# GeekTrack_SCH.net
KiCad netlist of a schematic drawn in Altium Designer
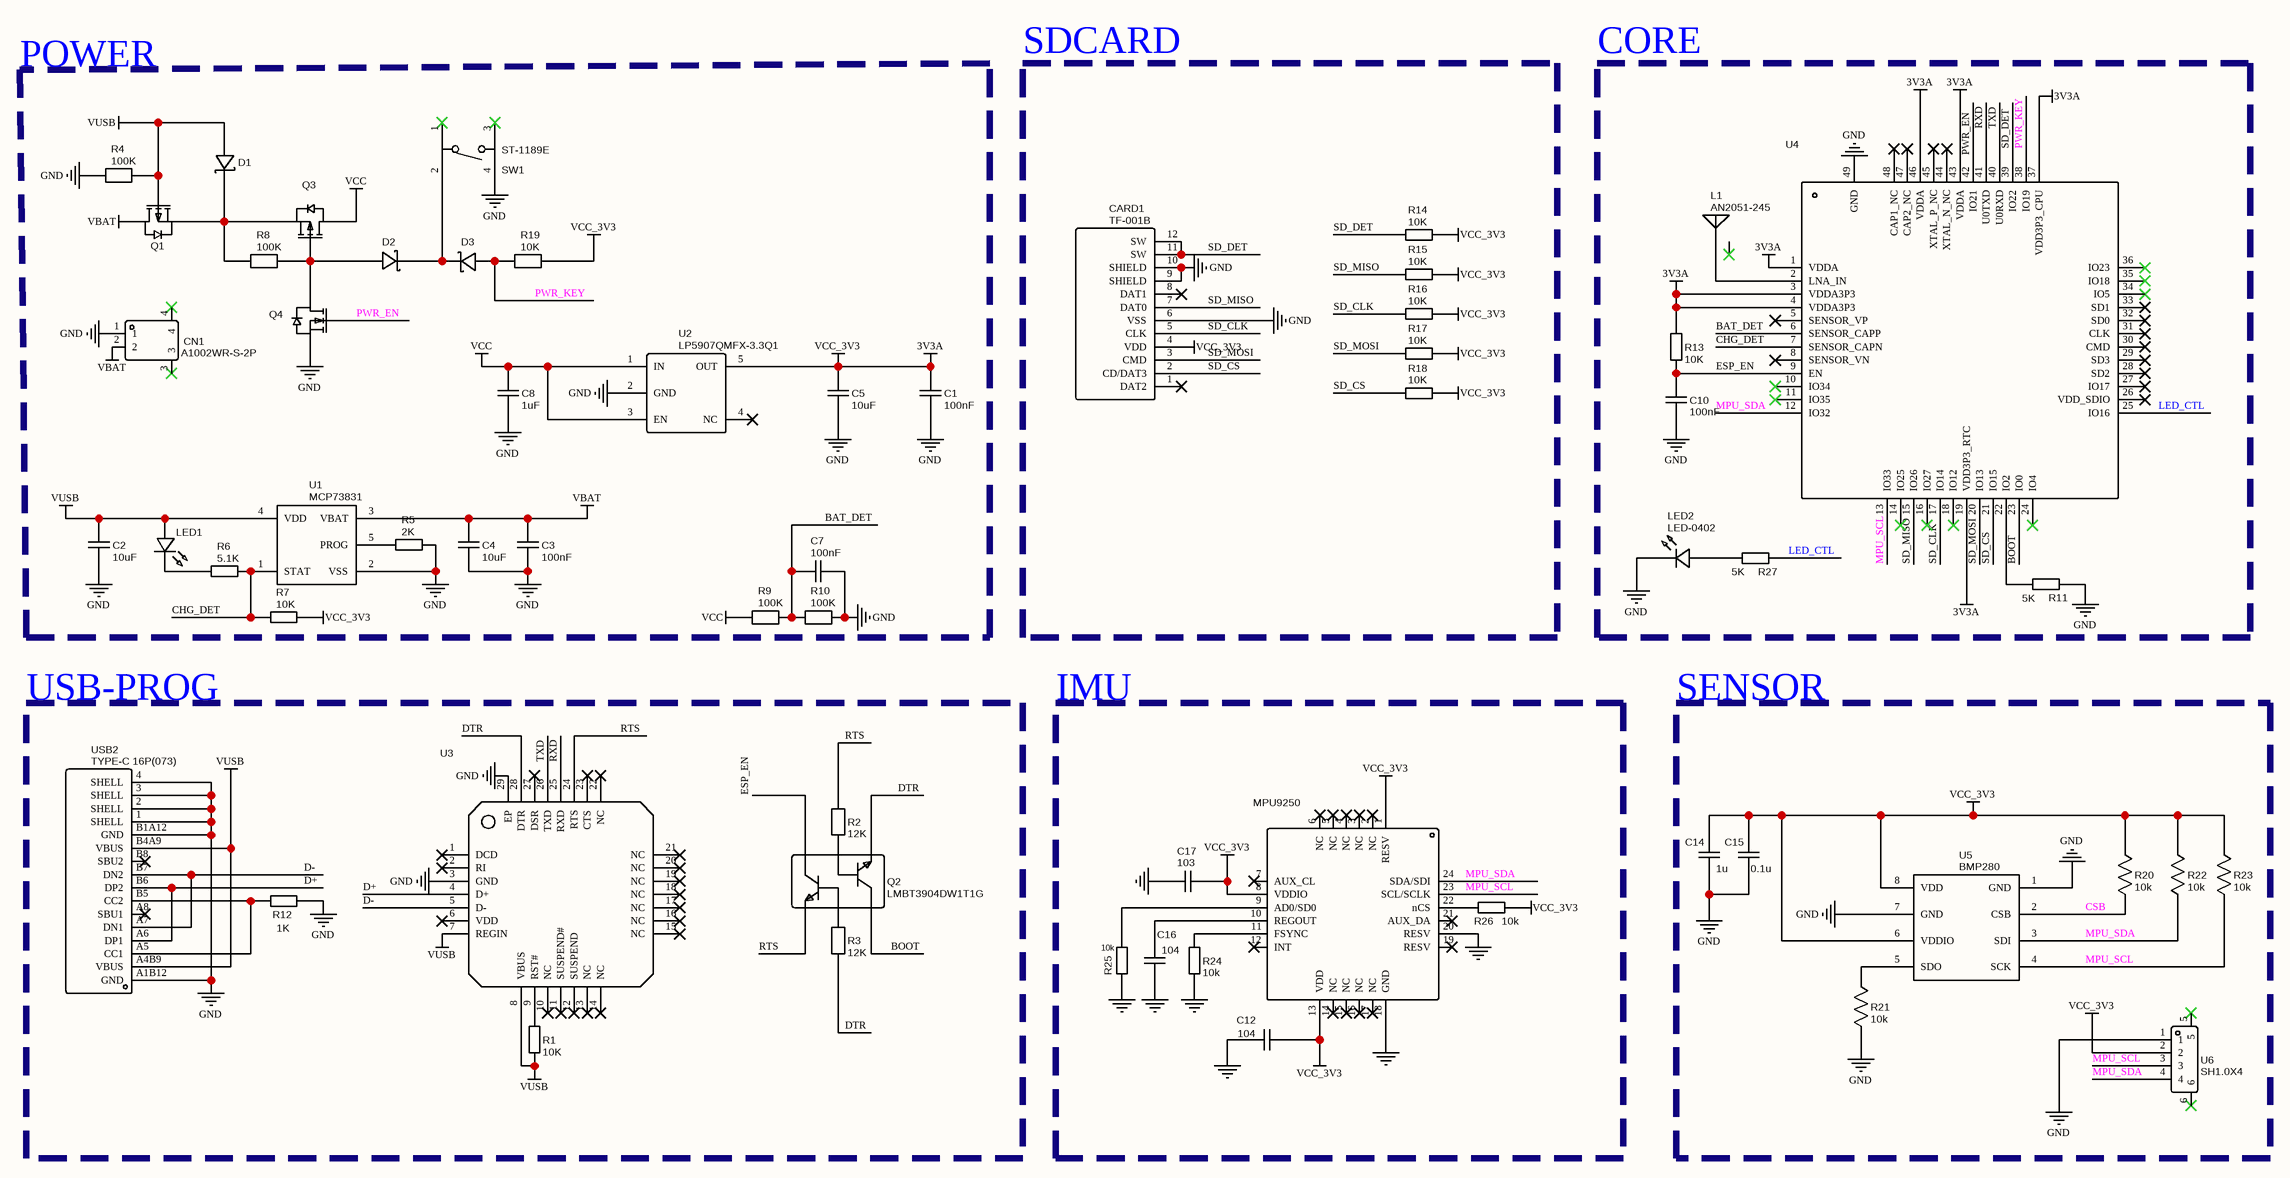
[diagram p0: GeekTrack_SCH.schdoc]

(export (version "E")
  (design (tool "Eeschema 10.0.6"))
  (components
    (comp (ref "C1")
      (value "100nF")
      (fields
        (field (name "BOM_SUPPLIER PART") "C541405")
        (field (name "BOM_MANUFACTURER PART") "CC0402KRX5R5BB104")
        (field (name "CONTRIBUTOR") "LCSC")
      )
      (libsource (lib "altium-import") (part "root_1_100nF_"))
    )
    (comp (ref "C2")
      (value "10uF")
      (fields
        (field (name "BOM_MANUFACTURER PART") "CL05A106MQ5NUNC")
        (field (name "BOM_SUPPLIER PART") "C15525")
      )
      (libsource (lib "altium-import") (part "root_1_10uF_"))
    )
    (comp (ref "C3")
      (value "100nF")
      (fields
        (field (name "BOM_SUPPLIER PART") "C541405")
        (field (name "BOM_MANUFACTURER PART") "CC0402KRX5R5BB104")
        (field (name "CONTRIBUTOR") "LCSC")
      )
      (libsource (lib "altium-import") (part "root_1_100nF_"))
    )
    (comp (ref "C4")
      (value "10uF")
      (fields
        (field (name "BOM_MANUFACTURER PART") "CL05A106MQ5NUNC")
        (field (name "BOM_SUPPLIER PART") "C15525")
      )
      (libsource (lib "altium-import") (part "root_1_10uF_"))
    )
    (comp (ref "C5")
      (value "10uF")
      (fields
        (field (name "BOM_SUPPLIER PART") "C141025")
        (field (name "BOM_MANUFACTURER PART") "C0402C105K9PAC7867")
        (field (name "CONTRIBUTOR") "LCSC")
      )
      (libsource (lib "altium-import") (part "root_0_10uF_"))
    )
    (comp (ref "C7")
      (value "100nF")
      (fields
        (field (name "BOM_SUPPLIER PART") "C541405")
        (field (name "BOM_MANUFACTURER PART") "CC0402KRX5R5BB104")
        (field (name "CONTRIBUTOR") "LCSC")
      )
      (libsource (lib "altium-import") (part "root_0_100nF_"))
    )
    (comp (ref "C8")
      (value "1uF")
      (fields
        (field (name "BOM_SUPPLIER PART") "C141025")
        (field (name "BOM_MANUFACTURER PART") "C0402C105K9PAC7867")
        (field (name "CONTRIBUTOR") "LCSC")
      )
      (libsource (lib "altium-import") (part "root_0_1uF_"))
    )
    (comp (ref "C10")
      (value "100nF")
      (fields
        (field (name "BOM_SUPPLIER PART") "C541405")
        (field (name "BOM_MANUFACTURER PART") "CC0402KRX5R5BB104")
        (field (name "CONTRIBUTOR") "LCSC")
      )
      (libsource (lib "altium-import") (part "root_1_100nF_"))
    )
    (comp (ref "C12")
      (value "104")
      (fields (field (name "BOM_MANUFACTURER PART") "?"))
      (libsource (lib "altium-import") (part "root_0_104_"))
    )
    (comp (ref "C14")
      (value "1u")
      (fields (field (name "CONTRIBUTOR") "LCEDA_Lib"))
      (libsource (lib "altium-import") (part "root_1_1u_"))
    )
    (comp (ref "C15")
      (value "0.1u")
      (fields (field (name "CONTRIBUTOR") "LCEDA_Lib"))
      (libsource (lib "altium-import") (part "root_1_0.1u_"))
    )
    (comp (ref "C16")
      (value "104")
      (fields (field (name "BOM_MANUFACTURER PART") "?"))
      (libsource (lib "altium-import") (part "root_1_104_"))
    )
    (comp (ref "C17")
      (value "103")
      (fields (field (name "BOM_MANUFACTURER PART") "?"))
      (libsource (lib "altium-import") (part "root_0_103_"))
    )
    (comp (ref "CARD1")
      (value "TF-001B")
      (fields (field (name "BOM_SUPPLIER PART") "C125617") (field (name "CONTRIBUTOR") "LCSC"))
      (libsource (lib "altium-import") (part "root_2_TF-001B_"))
    )
    (comp (ref "CN1")
      (value "A1002WR-S-2P")
      (fields (field (name "BOM_SUPPLIER PART") "C239520") (field (name "CONTRIBUTOR") "LCSC"))
      (libsource (lib "altium-import") (part "root_0_A1002WR-S-2P_"))
    )
    (comp (ref "D1")
      (value "B5819WS_C122855")
      (fields (field (name "BOM_MANUFACTURER PART") "B5819WS") (field (name "BOM_SUPPLIER PART") "C122855"))
      (libsource (lib "altium-import") (part "root_1_B5819WS_C122855_"))
    )
    (comp (ref "D2")
      (value "B5819WS_C122855")
      (fields (field (name "BOM_MANUFACTURER PART") "B5819WS") (field (name "BOM_SUPPLIER PART") "C122855"))
      (libsource (lib "altium-import") (part "root_2_B5819WS_C122855_"))
    )
    (comp (ref "D3")
      (value "B5819WS_C122855")
      (fields (field (name "BOM_MANUFACTURER PART") "B5819WS") (field (name "BOM_SUPPLIER PART") "C122855"))
      (libsource (lib "altium-import") (part "root_0_B5819WS_C122855_"))
    )
    (comp (ref "L1")
      (value "AN2051-245")
      (fields (field (name "BOM_SUPPLIER PART") "C99727"))
      (libsource (lib "altium-import") (part "root_0_AN2051-245_"))
    )
    (comp (ref "LED1")
      (value "LED-0603_R")
      (fields
        (field (name "BOM_MANUFACTURER PART") "19-217/R6C-AL1M2VY/3T")
        (field (name "BOM_SUPPLIER PART") "C72044")
        (field (name "CONTRIBUTOR") "LCEDA_01")
      )
      (libsource (lib "altium-import") (part "root_3_LED-0603_R_"))
    )
    (comp (ref "LED2")
      (value "LED-0402")
      (fields
        (field (name "BOM_SUPPLIER PART") "C917191")
        (field (name "BOM_MANUFACTURER PART") "TJ-S1005CL4T5ALC3DW-A5")
        (field (name "CONTRIBUTOR") "LCSC")
      )
      (libsource (lib "altium-import") (part "root_0_LED-0402_"))
    )
    (comp (ref "MPU9250")
      (value "MPU9250")
      (fields (field (name "BOM_MANUFACTURER PART") "?"))
      (libsource (lib "altium-import") (part "root_3_MPU9250_"))
    )
    (comp (ref "Q1")
      (value "AO3401A_C700954")
      (fields
        (field (name "BOM_SUPPLIER PART") "C700954")
        (field (name "BOM_MANUFACTURER PART") "AO3401A")
        (field (name "CONTRIBUTOR") "LCSC")
      )
      (libsource (lib "altium-import") (part "root_1_AO3401A_C700954_"))
    )
    (comp (ref "Q2")
      (value "LMBT3904DW1T1G")
      (fields (field (name "BOM_SUPPLIER PART") "C131781"))
      (libsource (lib "altium-import") (part "root_0_LMBT3904DW1T1G_"))
    )
    (comp (ref "Q3")
      (value "AO3401A_C700954")
      (fields
        (field (name "BOM_SUPPLIER PART") "C700954")
        (field (name "BOM_MANUFACTURER PART") "AO3401A")
        (field (name "CONTRIBUTOR") "LCSC")
      )
      (libsource (lib "altium-import") (part "root_3_AO3401A_C700954_"))
    )
    (comp (ref "Q4")
      (value "AO3400A_C700953")
      (fields
        (field (name "BOM_SUPPLIER PART") "C700953")
        (field (name "BOM_MANUFACTURER PART") "AO3400A")
        (field (name "CONTRIBUTOR") "LCSC")
      )
      (libsource (lib "altium-import") (part "root_2_AO3400A_C700953_"))
    )
    (comp (ref "R1")
      (value "10K")
      (fields
        (field (name "BOM_MANUFACTURER PART") "CR0402JF0103G")
        (field (name "BOM_SUPPLIER PART") "C100572")
      )
      (libsource (lib "altium-import") (part "root_1_10K_"))
    )
    (comp (ref "R2")
      (value "12K")
      (fields
        (field (name "BOM_SUPPLIER PART") "C881068")
        (field (name "BOM_MANUFACTURER PART") "CR0402F12K0Q10Z")
        (field (name "CONTRIBUTOR") "LCSC")
      )
      (libsource (lib "altium-import") (part "root_1_12K_"))
    )
    (comp (ref "R3")
      (value "12K")
      (fields
        (field (name "BOM_SUPPLIER PART") "C881068")
        (field (name "BOM_MANUFACTURER PART") "CR0402F12K0Q10Z")
        (field (name "CONTRIBUTOR") "LCSC")
      )
      (libsource (lib "altium-import") (part "root_1_12K_"))
    )
    (comp (ref "R4")
      (value "100K")
      (fields
        (field (name "BOM_SUPPLIER PART") "C881385")
        (field (name "BOM_MANUFACTURER PART") "CR0402F100KQ10Z")
        (field (name "CONTRIBUTOR") "LCSC")
      )
      (libsource (lib "altium-import") (part "root_0_100K_"))
    )
    (comp (ref "R5")
      (value "2K")
      (fields
        (field (name "BOM_MANUFACTURER PART") "CR0402FF2001G")
        (field (name "BOM_SUPPLIER PART") "C100291")
      )
      (libsource (lib "altium-import") (part "root_0_2K_"))
    )
    (comp (ref "R6")
      (value "5.1K")
      (fields
        (field (name "BOM_MANUFACTURER PART") "RC0402JR-071KL")
        (field (name "BOM_SUPPLIER PART") "C105637")
      )
      (libsource (lib "altium-import") (part "root_0_5.1K_"))
    )
    (comp (ref "R7")
      (value "10K")
      (fields
        (field (name "BOM_MANUFACTURER PART") "CR0402JF0103G")
        (field (name "BOM_SUPPLIER PART") "C100572")
      )
      (libsource (lib "") (part "root_0_10K__1"))
    )
    (comp (ref "R8")
      (value "100K")
      (fields
        (field (name "BOM_SUPPLIER PART") "C881385")
        (field (name "BOM_MANUFACTURER PART") "CR0402F100KQ10Z")
        (field (name "CONTRIBUTOR") "LCSC")
      )
      (libsource (lib "altium-import") (part "root_0_100K_"))
    )
    (comp (ref "R9")
      (value "100K")
      (fields
        (field (name "BOM_SUPPLIER PART") "C881385")
        (field (name "BOM_MANUFACTURER PART") "CR0402F100KQ10Z")
        (field (name "CONTRIBUTOR") "LCSC")
      )
      (libsource (lib "altium-import") (part "root_0_100K_"))
    )
    (comp (ref "R10")
      (value "100K")
      (fields
        (field (name "BOM_SUPPLIER PART") "C881385")
        (field (name "BOM_MANUFACTURER PART") "CR0402F100KQ10Z")
        (field (name "CONTRIBUTOR") "LCSC")
      )
      (libsource (lib "altium-import") (part "root_0_100K_"))
    )
    (comp (ref "R11")
      (value "5K")
      (fields
        (field (name "BOM_MANUFACTURER PART") "CR0402JF0103G")
        (field (name "BOM_SUPPLIER PART") "C100572")
      )
      (libsource (lib "altium-import") (part "root_2_5K_"))
    )
    (comp (ref "R12")
      (value "1K")
      (fields
        (field (name "BOM_MANUFACTURER PART") "RC0402JR-071KL")
        (field (name "BOM_SUPPLIER PART") "C105637")
      )
      (libsource (lib "altium-import") (part "root_0_1K_"))
    )
    (comp (ref "R13")
      (value "10K")
      (fields
        (field (name "BOM_MANUFACTURER PART") "CR0402JF0103G")
        (field (name "BOM_SUPPLIER PART") "C100572")
      )
      (libsource (lib "altium-import") (part "root_1_10K_"))
    )
    (comp (ref "R14")
      (value "10K")
      (fields
        (field (name "BOM_MANUFACTURER PART") "CR0402JF0103G")
        (field (name "BOM_SUPPLIER PART") "C100572")
      )
      (libsource (lib "altium-import") (part "root_2_10K_"))
    )
    (comp (ref "R15")
      (value "10K")
      (fields
        (field (name "BOM_MANUFACTURER PART") "CR0402JF0103G")
        (field (name "BOM_SUPPLIER PART") "C100572")
      )
      (libsource (lib "altium-import") (part "root_2_10K_"))
    )
    (comp (ref "R16")
      (value "10K")
      (fields
        (field (name "BOM_MANUFACTURER PART") "CR0402JF0103G")
        (field (name "BOM_SUPPLIER PART") "C100572")
      )
      (libsource (lib "altium-import") (part "root_2_10K_"))
    )
    (comp (ref "R17")
      (value "10K")
      (fields
        (field (name "BOM_MANUFACTURER PART") "CR0402JF0103G")
        (field (name "BOM_SUPPLIER PART") "C100572")
      )
      (libsource (lib "altium-import") (part "root_2_10K_"))
    )
    (comp (ref "R18")
      (value "10K")
      (fields
        (field (name "BOM_MANUFACTURER PART") "CR0402JF0103G")
        (field (name "BOM_SUPPLIER PART") "C100572")
      )
      (libsource (lib "altium-import") (part "root_2_10K_"))
    )
    (comp (ref "R19")
      (value "10K")
      (fields
        (field (name "BOM_SUPPLIER PART") "C881385")
        (field (name "BOM_MANUFACTURER PART") "CR0402F100KQ10Z")
        (field (name "CONTRIBUTOR") "LCSC")
      )
      (libsource (lib "altium-import") (part "root_0_10K_"))
    )
    (comp (ref "R20")
      (value "10k")
      (fields (field (name "CONTRIBUTOR") "LCEDA_Lib"))
      (libsource (lib "altium-import") (part "root_1_10k_"))
    )
    (comp (ref "R21")
      (value "10k")
      (fields (field (name "CONTRIBUTOR") "LCEDA_Lib"))
      (libsource (lib "altium-import") (part "root_1_10k_"))
    )
    (comp (ref "R22")
      (value "10k")
      (fields (field (name "CONTRIBUTOR") "LCEDA_Lib"))
      (libsource (lib "altium-import") (part "root_1_10k_"))
    )
    (comp (ref "R23")
      (value "10k")
      (fields (field (name "CONTRIBUTOR") "LCEDA_Lib"))
      (libsource (lib "altium-import") (part "root_1_10k_"))
    )
    (comp (ref "R24")
      (value "10k")
      (fields (field (name "BOM_MANUFACTURER PART") "?"))
      (libsource (lib "altium-import") (part "root_3_10k_"))
    )
    (comp (ref "R25")
      (value "10k")
      (fields (field (name "BOM_MANUFACTURER PART") "?"))
      (libsource (lib "") (part "root_1_10k__1"))
    )
    (comp (ref "R26")
      (value "10k")
      (fields (field (name "BOM_MANUFACTURER PART") "?"))
      (libsource (lib "altium-import") (part "root_0_10k_"))
    )
    (comp (ref "R27")
      (value "5K")
      (fields
        (field (name "BOM_MANUFACTURER PART") "CR0402JF0103G")
        (field (name "BOM_SUPPLIER PART") "C100572")
      )
      (libsource (lib "altium-import") (part "root_2_5K_"))
    )
    (comp (ref "SW1")
      (value "ST-1189E")
      (fields (field (name "BOM_SUPPLIER PART") "C589215") (field (name "CONTRIBUTOR") "LCSC"))
      (libsource (lib "altium-import") (part "root_1_ST-1189E_"))
    )
    (comp (ref "U1")
      (value "MCP73831")
      (fields
        (field (name "BOM_MANUFACTURER PART") "MCP73831T-2ATI/OT")
        (field (name "BOM_SUPPLIER PART") "C14879")
      )
      (libsource (lib "altium-import") (part "root_0_MCP73831_"))
    )
    (comp (ref "U2")
      (value "LP5907QMFX-3.3Q1")
      (fields (field (name "BOM_SUPPLIER PART") "C130005") (field (name "CONTRIBUTOR") "LCSC"))
      (libsource (lib "altium-import") (part "root_0_LP5907QMFX-3.3Q1_"))
    )
    (comp (ref "U3")
      (value "CP2102-GMR")
      (fields (field (name "BOM_SUPPLIER PART") "C6568"))
      (libsource (lib "altium-import") (part "root_0_CP2102-GMR_"))
    )
    (comp (ref "U4")
      (value "ESP32-PICO-D4")
      (fields (field (name "BOM_SUPPLIER PART") "C193707") (field (name "CONTRIBUTOR") "DGrain"))
      (libsource (lib "altium-import") (part "root_0_ESP32-PICO-D4_"))
    )
    (comp (ref "U5")
      (value "BMP280")
      (fields (field (name "BOM_SUPPLIER PART") "C83291"))
      (libsource (lib "altium-import") (part "root_0_BMP280_"))
    )
    (comp (ref "U6")
      (value "SH1.0X4")
      (fields
        (field (name "BOM_SUPPLIER PART") "C9900002342")
        (field (name "BOM_MANUFACTURER PART") "SH1.0X4卧贴")
        (field (name "CONTRIBUTOR") "LCSC")
      )
      (libsource (lib "altium-import") (part "root_0_SH1.0X4_"))
    )
    (comp (ref "USB2")
      (value "TYPE-C 16P(073)")
      (fields (field (name "BOM_SUPPLIER PART") "C668624") (field (name "CONTRIBUTOR") "LCSC"))
      (libsource (lib "altium-import") (part "root_2_TYPE-C 16P(073)_"))
    )
  )
  (nets
    (net (code "1") (name "/BAT_DET") (class "Default")
      (node (ref "C7") (pin "1") (pinfunction "1_1") (pintype "passive"))
      (node (ref "R10") (pin "1") (pinfunction "1_1") (pintype "passive"))
      (node (ref "R9") (pin "2") (pinfunction "2_2") (pintype "passive"))
      (node (ref "U4") (pin "6") (pinfunction "SENSOR_CAPP_6") (pintype "passive"))
    )
    (net (code "2") (name "/BOOT") (class "Default")
      (node (ref "Q2") (pin "3") (pinfunction "C_3") (pintype "passive"))
      (node (ref "U4") (pin "23") (pinfunction "IO0_23") (pintype "passive"))
    )
    (net (code "3") (name "/CHG_DET") (class "Default")
      (node (ref "R6") (pin "2") (pinfunction "2_2") (pintype "passive"))
      (node (ref "R7") (pin "1") (pinfunction "1_1") (pintype "passive"))
      (node (ref "U1") (pin "1") (pinfunction "STAT_1") (pintype "passive"))
      (node (ref "U4") (pin "7") (pinfunction "SENSOR_CAPN_7") (pintype "passive"))
    )
    (net (code "4") (name "/CSB") (class "Default")
      (node (ref "R20") (pin "1") (pinfunction "1_1") (pintype "passive"))
      (node (ref "U5") (pin "2") (pinfunction "CSB_2") (pintype "passive"))
    )
    (net (code "5") (name "/D+") (class "Default")
      (node (ref "U3") (pin "4") (pinfunction "D+_4") (pintype "passive"))
      (node (ref "USB2") (pin "A6") (pinfunction "DP1_A6") (pintype "passive"))
      (node (ref "USB2") (pin "B6") (pinfunction "DP2_B6") (pintype "passive"))
    )
    (net (code "6") (name "/D-") (class "Default")
      (node (ref "U3") (pin "5") (pinfunction "D-_5") (pintype "passive"))
      (node (ref "USB2") (pin "A7") (pinfunction "DN1_A7") (pintype "passive"))
      (node (ref "USB2") (pin "B7") (pinfunction "DN2_B7") (pintype "passive"))
    )
    (net (code "7") (name "/DTR") (class "Default")
      (node (ref "Q2") (pin "4") (pinfunction "E_4") (pintype "passive"))
      (node (ref "R3") (pin "1") (pinfunction "1_1") (pintype "passive"))
      (node (ref "U3") (pin "28") (pinfunction "DTR_28") (pintype "passive"))
    )
    (net (code "8") (name "/ESP_EN") (class "Default")
      (node (ref "C10") (pin "2") (pinfunction "2_2") (pintype "passive"))
      (node (ref "Q2") (pin "6") (pinfunction "C_6") (pintype "passive"))
      (node (ref "R13") (pin "1") (pinfunction "1_1") (pintype "passive"))
      (node (ref "U4") (pin "9") (pinfunction "EN_9") (pintype "passive"))
    )
    (net (code "9") (name "/LED_CTL") (class "Default")
      (node (ref "R27") (pin "1") (pinfunction "1_1") (pintype "passive"))
      (node (ref "U4") (pin "25") (pinfunction "IO16_25") (pintype "passive"))
    )
    (net (code "10") (name "/MPU_SCL") (class "Default")
      (node (ref "MPU9250") (pin "23") (pinfunction "SCL/SCLK_23") (pintype "passive"))
      (node (ref "R23") (pin "1") (pinfunction "1_1") (pintype "passive"))
      (node (ref "U4") (pin "13") (pinfunction "IO33_13") (pintype "passive"))
      (node (ref "U5") (pin "4") (pinfunction "SCK_4") (pintype "passive"))
      (node (ref "U6") (pin "3") (pinfunction "3_3") (pintype "passive"))
    )
    (net (code "11") (name "/MPU_SDA") (class "Default")
      (node (ref "MPU9250") (pin "24") (pinfunction "SDA/SDI_24") (pintype "passive"))
      (node (ref "R22") (pin "1") (pinfunction "1_1") (pintype "passive"))
      (node (ref "U4") (pin "12") (pinfunction "IO32_12") (pintype "passive"))
      (node (ref "U5") (pin "3") (pinfunction "SDI_3") (pintype "passive"))
      (node (ref "U6") (pin "4") (pinfunction "4_4") (pintype "passive"))
    )
    (net (code "12") (name "/PWR_EN") (class "Default")
      (node (ref "Q4") (pin "1") (pinfunction "G_1") (pintype "passive"))
      (node (ref "U4") (pin "42") (pinfunction "IO21_42") (pintype "passive"))
    )
    (net (code "13") (name "/PWR_KEY") (class "Default")
      (node (ref "D3") (pin "2") (pinfunction "A_2") (pintype "passive"))
      (node (ref "R19") (pin "1") (pinfunction "1_1") (pintype "passive"))
      (node (ref "U4") (pin "38") (pinfunction "IO19_38") (pintype "passive"))
    )
    (net (code "14") (name "/RTS") (class "Default")
      (node (ref "Q2") (pin "1") (pinfunction "E_1") (pintype "passive"))
      (node (ref "R2") (pin "2") (pinfunction "2_2") (pintype "passive"))
      (node (ref "U3") (pin "24") (pinfunction "RTS_24") (pintype "passive"))
    )
    (net (code "15") (name "/RXD") (class "Default")
      (node (ref "U3") (pin "25") (pinfunction "RXD_25") (pintype "passive"))
      (node (ref "U4") (pin "41") (pinfunction "U0TXD_41") (pintype "passive"))
    )
    (net (code "16") (name "/SD_CLK") (class "Default")
      (node (ref "CARD1") (pin "5") (pinfunction "CLK_5") (pintype "passive"))
      (node (ref "R16") (pin "2") (pinfunction "2_2") (pintype "passive"))
      (node (ref "U4") (pin "17") (pinfunction "IO14_17") (pintype "passive"))
    )
    (net (code "17") (name "/SD_CS") (class "Default")
      (node (ref "CARD1") (pin "2") (pinfunction "CD/DAT3_2") (pintype "passive"))
      (node (ref "R18") (pin "2") (pinfunction "2_2") (pintype "passive"))
      (node (ref "U4") (pin "21") (pinfunction "IO15_21") (pintype "passive"))
    )
    (net (code "18") (name "/SD_DET") (class "Default")
      (node (ref "CARD1") (pin "11") (pinfunction "SW_11") (pintype "passive"))
      (node (ref "CARD1") (pin "12") (pinfunction "SW_12") (pintype "passive"))
      (node (ref "R14") (pin "2") (pinfunction "2_2") (pintype "passive"))
      (node (ref "U4") (pin "39") (pinfunction "IO22_39") (pintype "passive"))
    )
    (net (code "19") (name "/SD_MISO") (class "Default")
      (node (ref "CARD1") (pin "7") (pinfunction "DAT0_7") (pintype "passive"))
      (node (ref "R15") (pin "2") (pinfunction "2_2") (pintype "passive"))
      (node (ref "U4") (pin "15") (pinfunction "IO26_15") (pintype "passive"))
    )
    (net (code "20") (name "/SD_MOSI") (class "Default")
      (node (ref "CARD1") (pin "3") (pinfunction "CMD_3") (pintype "passive"))
      (node (ref "R17") (pin "2") (pinfunction "2_2") (pintype "passive"))
      (node (ref "U4") (pin "20") (pinfunction "IO13_20") (pintype "passive"))
    )
    (net (code "21") (name "/TXD") (class "Default")
      (node (ref "U3") (pin "26") (pinfunction "TXD_26") (pintype "passive"))
      (node (ref "U4") (pin "40") (pinfunction "U0RXD_40") (pintype "passive"))
    )
    (net (code "22") (name "3V3A") (class "Default")
      (node (ref "C1") (pin "2") (pinfunction "2_2") (pintype "passive"))
      (node (ref "C12") (pin "2") (pinfunction "2_2") (pintype "passive"))
      (node (ref "C14") (pin "2") (pinfunction "2_2") (pintype "passive"))
      (node (ref "C15") (pin "2") (pinfunction "2_2") (pintype "passive"))
      (node (ref "C17") (pin "2") (pinfunction "2_2") (pintype "passive"))
      (node (ref "C5") (pin "2") (pinfunction "2_2") (pintype "passive"))
      (node (ref "CARD1") (pin "4") (pinfunction "VDD_4") (pintype "passive"))
      (node (ref "MPU9250") (pin "1") (pinfunction "RESV_1") (pintype "passive"))
      (node (ref "MPU9250") (pin "13") (pinfunction "VDD_13") (pintype "passive"))
      (node (ref "MPU9250") (pin "8") (pinfunction "VDDIO_8") (pintype "passive"))
      (node (ref "R13") (pin "2") (pinfunction "2_2") (pintype "passive"))
      (node (ref "R14") (pin "1") (pinfunction "1_1") (pintype "passive"))
      (node (ref "R15") (pin "1") (pinfunction "1_1") (pintype "passive"))
      (node (ref "R16") (pin "1") (pinfunction "1_1") (pintype "passive"))
      (node (ref "R17") (pin "1") (pinfunction "1_1") (pintype "passive"))
      (node (ref "R18") (pin "1") (pinfunction "1_1") (pintype "passive"))
      (node (ref "R19") (pin "2") (pinfunction "2_2") (pintype "passive"))
      (node (ref "R20") (pin "2") (pinfunction "2_2") (pintype "passive"))
      (node (ref "R22") (pin "2") (pinfunction "2_2") (pintype "passive"))
      (node (ref "R23") (pin "2") (pinfunction "2_2") (pintype "passive"))
      (node (ref "R26") (pin "2") (pinfunction "2_2") (pintype "passive"))
      (node (ref "R7") (pin "2") (pinfunction "2_2") (pintype "passive"))
      (node (ref "U2") (pin "5") (pinfunction "OUT_5") (pintype "passive"))
      (node (ref "U4") (pin "1") (pinfunction "VDDA_1") (pintype "passive"))
      (node (ref "U4") (pin "19") (pinfunction "VDD3P3_RTC_19") (pintype "passive"))
      (node (ref "U4") (pin "3") (pinfunction "VDDA3P3_3") (pintype "passive"))
      (node (ref "U4") (pin "37") (pinfunction "VDD3P3_CPU_37") (pintype "passive"))
      (node (ref "U4") (pin "4") (pinfunction "VDDA3P3_4") (pintype "passive"))
      (node (ref "U4") (pin "43") (pinfunction "VDDA_43") (pintype "passive"))
      (node (ref "U4") (pin "46") (pinfunction "VDDA_46") (pintype "passive"))
      (node (ref "U5") (pin "6") (pinfunction "VDDIO_6") (pintype "passive"))
      (node (ref "U5") (pin "8") (pinfunction "VDD_8") (pintype "passive"))
      (node (ref "U6") (pin "2") (pinfunction "2_2") (pintype "passive"))
    )
    (net (code "23") (name "GND") (class "Default")
      (node (ref "C1") (pin "1") (pinfunction "1_1") (pintype "passive"))
      (node (ref "C10") (pin "1") (pinfunction "1_1") (pintype "passive"))
      (node (ref "C12") (pin "1") (pinfunction "1_1") (pintype "passive"))
      (node (ref "C14") (pin "1") (pinfunction "1_1") (pintype "passive"))
      (node (ref "C15") (pin "1") (pinfunction "1_1") (pintype "passive"))
      (node (ref "C16") (pin "1") (pinfunction "1_1") (pintype "passive"))
      (node (ref "C17") (pin "1") (pinfunction "1_1") (pintype "passive"))
      (node (ref "C2") (pin "1") (pinfunction "1_1") (pintype "passive"))
      (node (ref "C3") (pin "1") (pinfunction "1_1") (pintype "passive"))
      (node (ref "C4") (pin "1") (pinfunction "1_1") (pintype "passive"))
      (node (ref "C5") (pin "1") (pinfunction "1_1") (pintype "passive"))
      (node (ref "C7") (pin "2") (pinfunction "2_2") (pintype "passive"))
      (node (ref "C8") (pin "1") (pinfunction "1_1") (pintype "passive"))
      (node (ref "CARD1") (pin "10") (pinfunction "SHIELD_10") (pintype "passive"))
      (node (ref "CARD1") (pin "6") (pinfunction "VSS_6") (pintype "passive"))
      (node (ref "CARD1") (pin "9") (pinfunction "SHIELD_9") (pintype "passive"))
      (node (ref "CN1") (pin "1") (pinfunction "1_1") (pintype "passive"))
      (node (ref "LED2") (pin "1") (pinfunction "K_1") (pintype "passive"))
      (node (ref "MPU9250") (pin "18") (pinfunction "GND_18") (pintype "passive"))
      (node (ref "MPU9250") (pin "20") (pinfunction "RESV_20") (pintype "passive"))
      (node (ref "Q4") (pin "2") (pinfunction "S_2") (pintype "passive"))
      (node (ref "R10") (pin "2") (pinfunction "2_2") (pintype "passive"))
      (node (ref "R11") (pin "1") (pinfunction "1_1") (pintype "passive"))
      (node (ref "R12") (pin "2") (pinfunction "2_2") (pintype "passive"))
      (node (ref "R21") (pin "1") (pinfunction "1_1") (pintype "passive"))
      (node (ref "R24") (pin "2") (pinfunction "2_2") (pintype "passive"))
      (node (ref "R25") (pin "1") (pinfunction "1_1") (pintype "passive"))
      (node (ref "R4") (pin "1") (pinfunction "1_1") (pintype "passive"))
      (node (ref "R5") (pin "2") (pinfunction "2_2") (pintype "passive"))
      (node (ref "SW1") (pin "4") (pinfunction "4_4") (pintype "passive"))
      (node (ref "U1") (pin "2") (pinfunction "VSS_2") (pintype "passive"))
      (node (ref "U2") (pin "2") (pinfunction "GND_2") (pintype "passive"))
      (node (ref "U3") (pin "29") (pinfunction "EP_29") (pintype "passive"))
      (node (ref "U3") (pin "3") (pinfunction "GND_3") (pintype "passive"))
      (node (ref "U4") (pin "49") (pinfunction "GND_49") (pintype "passive"))
      (node (ref "U5") (pin "1") (pinfunction "GND_1") (pintype "passive"))
      (node (ref "U5") (pin "7") (pinfunction "GND_7") (pintype "passive"))
      (node (ref "U6") (pin "1") (pinfunction "1_1") (pintype "passive"))
      (node (ref "USB2") (pin "1") (pinfunction "SHELL_1") (pintype "passive"))
      (node (ref "USB2") (pin "2") (pinfunction "SHELL_2") (pintype "passive"))
      (node (ref "USB2") (pin "3") (pinfunction "SHELL_3") (pintype "passive"))
      (node (ref "USB2") (pin "4") (pinfunction "SHELL_4") (pintype "passive"))
      (node (ref "USB2") (pin "A1B12") (pinfunction "GND_A1B12") (pintype "passive"))
      (node (ref "USB2") (pin "B1A12") (pinfunction "GND_B1A12") (pintype "passive"))
    )
    (net (code "24") (name "Net-(D1-K)") (class "Default")
      (node (ref "D1") (pin "1") (pinfunction "K_1") (pintype "passive"))
      (node (ref "Q1") (pin "2") (pinfunction "S_2") (pintype "passive"))
      (node (ref "Q3") (pin "2") (pinfunction "S_2") (pintype "passive"))
      (node (ref "R8") (pin "1") (pinfunction "1_1") (pintype "passive"))
    )
    (net (code "25") (name "Net-(D2-A)") (class "Default")
      (node (ref "D2") (pin "2") (pinfunction "A_2") (pintype "passive"))
      (node (ref "Q3") (pin "1") (pinfunction "G_1") (pintype "passive"))
      (node (ref "Q4") (pin "3") (pinfunction "D_3") (pintype "passive"))
      (node (ref "R8") (pin "2") (pinfunction "2_2") (pintype "passive"))
    )
    (net (code "26") (name "Net-(D2-K)") (class "Default")
      (node (ref "D2") (pin "1") (pinfunction "K_1") (pintype "passive"))
      (node (ref "D3") (pin "1") (pinfunction "K_1") (pintype "passive"))
      (node (ref "SW1") (pin "2") (pinfunction "2_2") (pintype "passive"))
    )
    (net (code "27") (name "Net-(L1-ANT)") (class "Default")
      (node (ref "L1") (pin "1") (pinfunction "ANT_1") (pintype "passive"))
      (node (ref "U4") (pin "2") (pinfunction "LNA_IN_2") (pintype "passive"))
    )
    (net (code "28") (name "Net-(LED1-Pad2)") (class "Default")
      (node (ref "LED1") (pin "2") (pinfunction "2_2") (pintype "passive"))
      (node (ref "R6") (pin "1") (pinfunction "1_1") (pintype "passive"))
    )
    (net (code "29") (name "Net-(LED2-A)") (class "Default")
      (node (ref "LED2") (pin "2") (pinfunction "A_2") (pintype "passive"))
      (node (ref "R27") (pin "2") (pinfunction "2_2") (pintype "passive"))
    )
    (net (code "30") (name "Net-(MPU9250-AD0{slash}SD0)") (class "Default")
      (node (ref "MPU9250") (pin "9") (pinfunction "AD0/SD0_9") (pintype "passive"))
      (node (ref "R25") (pin "2") (pinfunction "2_2") (pintype "passive"))
    )
    (net (code "31") (name "Net-(MPU9250-FSYNC)") (class "Default")
      (node (ref "MPU9250") (pin "11") (pinfunction "FSYNC_11") (pintype "passive"))
      (node (ref "R24") (pin "1") (pinfunction "1_1") (pintype "passive"))
    )
    (net (code "32") (name "Net-(MPU9250-REGOUT)") (class "Default")
      (node (ref "C16") (pin "2") (pinfunction "2_2") (pintype "passive"))
      (node (ref "MPU9250") (pin "10") (pinfunction "REGOUT_10") (pintype "passive"))
    )
    (net (code "33") (name "Net-(MPU9250-nCS)") (class "Default")
      (node (ref "MPU9250") (pin "22") (pinfunction "nCS_22") (pintype "passive"))
      (node (ref "R26") (pin "1") (pinfunction "1_1") (pintype "passive"))
    )
    (net (code "34") (name "Net-(Q2-B-Pad2)") (class "Default")
      (node (ref "Q2") (pin "2") (pinfunction "B_2") (pintype "passive"))
      (node (ref "R3") (pin "2") (pinfunction "2_2") (pintype "passive"))
    )
    (net (code "35") (name "Net-(Q2-B-Pad5)") (class "Default")
      (node (ref "Q2") (pin "5") (pinfunction "B_5") (pintype "passive"))
      (node (ref "R2") (pin "1") (pinfunction "1_1") (pintype "passive"))
    )
    (net (code "36") (name "Net-(U1-PROG)") (class "Default")
      (node (ref "R5") (pin "1") (pinfunction "1_1") (pintype "passive"))
      (node (ref "U1") (pin "5") (pinfunction "PROG_5") (pintype "passive"))
    )
    (net (code "37") (name "Net-(U3-RST#)") (class "Default")
      (node (ref "R1") (pin "2") (pinfunction "2_2") (pintype "passive"))
      (node (ref "U3") (pin "9") (pinfunction "RST#_9") (pintype "passive"))
    )
    (net (code "38") (name "Net-(U4-IO2)") (class "Default")
      (node (ref "R11") (pin "2") (pinfunction "2_2") (pintype "passive"))
      (node (ref "U4") (pin "22") (pinfunction "IO2_22") (pintype "passive"))
    )
    (net (code "39") (name "Net-(U5-SDO)") (class "Default")
      (node (ref "R21") (pin "2") (pinfunction "2_2") (pintype "passive"))
      (node (ref "U5") (pin "5") (pinfunction "SDO_5") (pintype "passive"))
    )
    (net (code "40") (name "Net-(USB2-CC1)") (class "Default")
      (node (ref "R12") (pin "1") (pinfunction "1_1") (pintype "passive"))
      (node (ref "USB2") (pin "A5") (pinfunction "CC1_A5") (pintype "passive"))
      (node (ref "USB2") (pin "B5") (pinfunction "CC2_B5") (pintype "passive"))
    )
    (net (code "41") (name "VBAT") (class "Default")
      (node (ref "C3") (pin "2") (pinfunction "2_2") (pintype "passive"))
      (node (ref "C4") (pin "2") (pinfunction "2_2") (pintype "passive"))
      (node (ref "CN1") (pin "2") (pinfunction "2_2") (pintype "passive"))
      (node (ref "Q1") (pin "3") (pinfunction "D_3") (pintype "passive"))
      (node (ref "U1") (pin "3") (pinfunction "VBAT_3") (pintype "passive"))
    )
    (net (code "42") (name "VCC") (class "Default")
      (node (ref "C8") (pin "2") (pinfunction "2_2") (pintype "passive"))
      (node (ref "Q3") (pin "3") (pinfunction "D_3") (pintype "passive"))
      (node (ref "R9") (pin "1") (pinfunction "1_1") (pintype "passive"))
      (node (ref "U2") (pin "1") (pinfunction "IN_1") (pintype "passive"))
      (node (ref "U2") (pin "3") (pinfunction "EN_3") (pintype "passive"))
    )
    (net (code "43") (name "VUSB") (class "Default")
      (node (ref "C2") (pin "2") (pinfunction "2_2") (pintype "passive"))
      (node (ref "D1") (pin "2") (pinfunction "A_2") (pintype "passive"))
      (node (ref "LED1") (pin "1") (pinfunction "1_1") (pintype "passive"))
      (node (ref "Q1") (pin "1") (pinfunction "G_1") (pintype "passive"))
      (node (ref "R1") (pin "1") (pinfunction "1_1") (pintype "passive"))
      (node (ref "R4") (pin "2") (pinfunction "2_2") (pintype "passive"))
      (node (ref "U1") (pin "4") (pinfunction "VDD_4") (pintype "passive"))
      (node (ref "U3") (pin "7") (pinfunction "REGIN_7") (pintype "passive"))
      (node (ref "U3") (pin "8") (pinfunction "VBUS_8") (pintype "passive"))
      (node (ref "USB2") (pin "A4B9") (pinfunction "VBUS_A4B9") (pintype "passive"))
      (node (ref "USB2") (pin "B4A9") (pinfunction "VBUS_B4A9") (pintype "passive"))
    )
    (net (code "44") (name "unconnected-(CARD1-DAT1-Pad8)") (class "Default")
      (node (ref "CARD1") (pin "8") (pinfunction "DAT1_8") (pintype "passive+no_connect"))
    )
    (net (code "45") (name "unconnected-(CARD1-DAT2-Pad1)") (class "Default")
      (node (ref "CARD1") (pin "1") (pinfunction "DAT2_1") (pintype "passive+no_connect"))
    )
    (net (code "46") (name "unconnected-(CN1-Pad3)") (class "Default")
      (node (ref "CN1") (pin "3") (pinfunction "3_3") (pintype "passive+no_connect"))
    )
    (net (code "47") (name "unconnected-(CN1-Pad4)") (class "Default")
      (node (ref "CN1") (pin "4") (pinfunction "4_4") (pintype "passive+no_connect"))
    )
    (net (code "48") (name "unconnected-(L1-Pad2)") (class "Default")
      (node (ref "L1") (pin "2") (pinfunction "2_2") (pintype "passive+no_connect"))
    )
    (net (code "49") (name "unconnected-(MPU9250-AUX_CL-Pad7)") (class "Default")
      (node (ref "MPU9250") (pin "7") (pinfunction "AUX_CL_7") (pintype "passive+no_connect"))
    )
    (net (code "50") (name "unconnected-(MPU9250-AUX_DA-Pad21)") (class "Default")
      (node (ref "MPU9250") (pin "21") (pinfunction "AUX_DA_21") (pintype "passive+no_connect"))
    )
    (net (code "51") (name "unconnected-(MPU9250-INT-Pad12)") (class "Default")
      (node (ref "MPU9250") (pin "12") (pinfunction "INT_12") (pintype "passive+no_connect"))
    )
    (net (code "52") (name "unconnected-(MPU9250-NC-Pad2)") (class "Default")
      (node (ref "MPU9250") (pin "2") (pinfunction "NC_2") (pintype "passive+no_connect"))
    )
    (net (code "53") (name "unconnected-(MPU9250-NC-Pad3)") (class "Default")
      (node (ref "MPU9250") (pin "3") (pinfunction "NC_3") (pintype "passive+no_connect"))
    )
    (net (code "54") (name "unconnected-(MPU9250-NC-Pad4)") (class "Default")
      (node (ref "MPU9250") (pin "4") (pinfunction "NC_4") (pintype "passive+no_connect"))
    )
    (net (code "55") (name "unconnected-(MPU9250-NC-Pad5)") (class "Default")
      (node (ref "MPU9250") (pin "5") (pinfunction "NC_5") (pintype "passive+no_connect"))
    )
    (net (code "56") (name "unconnected-(MPU9250-NC-Pad6)") (class "Default")
      (node (ref "MPU9250") (pin "6") (pinfunction "NC_6") (pintype "passive+no_connect"))
    )
    (net (code "57") (name "unconnected-(MPU9250-NC-Pad14)") (class "Default")
      (node (ref "MPU9250") (pin "14") (pinfunction "NC_14") (pintype "passive+no_connect"))
    )
    (net (code "58") (name "unconnected-(MPU9250-NC-Pad15)") (class "Default")
      (node (ref "MPU9250") (pin "15") (pinfunction "NC_15") (pintype "passive+no_connect"))
    )
    (net (code "59") (name "unconnected-(MPU9250-NC-Pad16)") (class "Default")
      (node (ref "MPU9250") (pin "16") (pinfunction "NC_16") (pintype "passive+no_connect"))
    )
    (net (code "60") (name "unconnected-(MPU9250-NC-Pad17)") (class "Default")
      (node (ref "MPU9250") (pin "17") (pinfunction "NC_17") (pintype "passive+no_connect"))
    )
    (net (code "61") (name "unconnected-(MPU9250-RESV-Pad19)") (class "Default")
      (node (ref "MPU9250") (pin "19") (pinfunction "RESV_19") (pintype "passive+no_connect"))
    )
    (net (code "62") (name "unconnected-(SW1-Pad1)") (class "Default")
      (node (ref "SW1") (pin "1") (pinfunction "1_1") (pintype "passive+no_connect"))
    )
    (net (code "63") (name "unconnected-(SW1-Pad3)") (class "Default")
      (node (ref "SW1") (pin "3") (pinfunction "3_3") (pintype "passive+no_connect"))
    )
    (net (code "64") (name "unconnected-(U2-NC-Pad4)") (class "Default")
      (node (ref "U2") (pin "4") (pinfunction "NC_4") (pintype "passive+no_connect"))
    )
    (net (code "65") (name "unconnected-(U3-CTS-Pad23)") (class "Default")
      (node (ref "U3") (pin "23") (pinfunction "CTS_23") (pintype "passive+no_connect"))
    )
    (net (code "66") (name "unconnected-(U3-DCD-Pad1)") (class "Default")
      (node (ref "U3") (pin "1") (pinfunction "DCD_1") (pintype "passive+no_connect"))
    )
    (net (code "67") (name "unconnected-(U3-DSR-Pad27)") (class "Default")
      (node (ref "U3") (pin "27") (pinfunction "DSR_27") (pintype "passive+no_connect"))
    )
    (net (code "68") (name "unconnected-(U3-NC-Pad10)") (class "Default")
      (node (ref "U3") (pin "10") (pinfunction "NC_10") (pintype "passive+no_connect"))
    )
    (net (code "69") (name "unconnected-(U3-NC-Pad13)") (class "Default")
      (node (ref "U3") (pin "13") (pinfunction "NC_13") (pintype "passive+no_connect"))
    )
    (net (code "70") (name "unconnected-(U3-NC-Pad14)") (class "Default")
      (node (ref "U3") (pin "14") (pinfunction "NC_14") (pintype "passive+no_connect"))
    )
    (net (code "71") (name "unconnected-(U3-NC-Pad15)") (class "Default")
      (node (ref "U3") (pin "15") (pinfunction "NC_15") (pintype "passive+no_connect"))
    )
    (net (code "72") (name "unconnected-(U3-NC-Pad16)") (class "Default")
      (node (ref "U3") (pin "16") (pinfunction "NC_16") (pintype "passive+no_connect"))
    )
    (net (code "73") (name "unconnected-(U3-NC-Pad17)") (class "Default")
      (node (ref "U3") (pin "17") (pinfunction "NC_17") (pintype "passive+no_connect"))
    )
    (net (code "74") (name "unconnected-(U3-NC-Pad18)") (class "Default")
      (node (ref "U3") (pin "18") (pinfunction "NC_18") (pintype "passive+no_connect"))
    )
    (net (code "75") (name "unconnected-(U3-NC-Pad19)") (class "Default")
      (node (ref "U3") (pin "19") (pinfunction "NC_19") (pintype "passive+no_connect"))
    )
    (net (code "76") (name "unconnected-(U3-NC-Pad20)") (class "Default")
      (node (ref "U3") (pin "20") (pinfunction "NC_20") (pintype "passive+no_connect"))
    )
    (net (code "77") (name "unconnected-(U3-NC-Pad21)") (class "Default")
      (node (ref "U3") (pin "21") (pinfunction "NC_21") (pintype "passive+no_connect"))
    )
    (net (code "78") (name "unconnected-(U3-NC-Pad22)") (class "Default")
      (node (ref "U3") (pin "22") (pinfunction "NC_22") (pintype "passive+no_connect"))
    )
    (net (code "79") (name "unconnected-(U3-RI-Pad2)") (class "Default")
      (node (ref "U3") (pin "2") (pinfunction "RI_2") (pintype "passive+no_connect"))
    )
    (net (code "80") (name "unconnected-(U3-SUSPEND#-Pad11)") (class "Default")
      (node (ref "U3") (pin "11") (pinfunction "SUSPEND#_11") (pintype "passive+no_connect"))
    )
    (net (code "81") (name "unconnected-(U3-SUSPEND-Pad12)") (class "Default")
      (node (ref "U3") (pin "12") (pinfunction "SUSPEND_12") (pintype "passive+no_connect"))
    )
    (net (code "82") (name "unconnected-(U3-VDD-Pad6)") (class "Default")
      (node (ref "U3") (pin "6") (pinfunction "VDD_6") (pintype "passive+no_connect"))
    )
    (net (code "83") (name "unconnected-(U4-CAP1_NC-Pad48)") (class "Default")
      (node (ref "U4") (pin "48") (pinfunction "CAP1_NC_48") (pintype "passive+no_connect"))
    )
    (net (code "84") (name "unconnected-(U4-CAP2_NC-Pad47)") (class "Default")
      (node (ref "U4") (pin "47") (pinfunction "CAP2_NC_47") (pintype "passive+no_connect"))
    )
    (net (code "85") (name "unconnected-(U4-CLK-Pad31)") (class "Default")
      (node (ref "U4") (pin "31") (pinfunction "CLK_31") (pintype "passive+no_connect"))
    )
    (net (code "86") (name "unconnected-(U4-CMD-Pad30)") (class "Default")
      (node (ref "U4") (pin "30") (pinfunction "CMD_30") (pintype "passive+no_connect"))
    )
    (net (code "87") (name "unconnected-(U4-IO4-Pad24)") (class "Default")
      (node (ref "U4") (pin "24") (pinfunction "IO4_24") (pintype "passive+no_connect"))
    )
    (net (code "88") (name "unconnected-(U4-IO5-Pad34)") (class "Default")
      (node (ref "U4") (pin "34") (pinfunction "IO5_34") (pintype "passive+no_connect"))
    )
    (net (code "89") (name "unconnected-(U4-IO12-Pad18)") (class "Default")
      (node (ref "U4") (pin "18") (pinfunction "IO12_18") (pintype "passive+no_connect"))
    )
    (net (code "90") (name "unconnected-(U4-IO17-Pad27)") (class "Default")
      (node (ref "U4") (pin "27") (pinfunction "IO17_27") (pintype "passive+no_connect"))
    )
    (net (code "91") (name "unconnected-(U4-IO18-Pad35)") (class "Default")
      (node (ref "U4") (pin "35") (pinfunction "IO18_35") (pintype "passive+no_connect"))
    )
    (net (code "92") (name "unconnected-(U4-IO23-Pad36)") (class "Default")
      (node (ref "U4") (pin "36") (pinfunction "IO23_36") (pintype "passive+no_connect"))
    )
    (net (code "93") (name "unconnected-(U4-IO25-Pad14)") (class "Default")
      (node (ref "U4") (pin "14") (pinfunction "IO25_14") (pintype "passive+no_connect"))
    )
    (net (code "94") (name "unconnected-(U4-IO27-Pad16)") (class "Default")
      (node (ref "U4") (pin "16") (pinfunction "IO27_16") (pintype "passive+no_connect"))
    )
    (net (code "95") (name "unconnected-(U4-IO34-Pad10)") (class "Default")
      (node (ref "U4") (pin "10") (pinfunction "IO34_10") (pintype "passive+no_connect"))
    )
    (net (code "96") (name "unconnected-(U4-IO35-Pad11)") (class "Default")
      (node (ref "U4") (pin "11") (pinfunction "IO35_11") (pintype "passive+no_connect"))
    )
    (net (code "97") (name "unconnected-(U4-SD0-Pad32)") (class "Default")
      (node (ref "U4") (pin "32") (pinfunction "SD0_32") (pintype "passive+no_connect"))
    )
    (net (code "98") (name "unconnected-(U4-SD1-Pad33)") (class "Default")
      (node (ref "U4") (pin "33") (pinfunction "SD1_33") (pintype "passive+no_connect"))
    )
    (net (code "99") (name "unconnected-(U4-SD2-Pad28)") (class "Default")
      (node (ref "U4") (pin "28") (pinfunction "SD2_28") (pintype "passive+no_connect"))
    )
    (net (code "100") (name "unconnected-(U4-SD3-Pad29)") (class "Default")
      (node (ref "U4") (pin "29") (pinfunction "SD3_29") (pintype "passive+no_connect"))
    )
    (net (code "101") (name "unconnected-(U4-SENSOR_VN-Pad8)") (class "Default")
      (node (ref "U4") (pin "8") (pinfunction "SENSOR_VN_8") (pintype "passive+no_connect"))
    )
    (net (code "102") (name "unconnected-(U4-SENSOR_VP-Pad5)") (class "Default")
      (node (ref "U4") (pin "5") (pinfunction "SENSOR_VP_5") (pintype "passive+no_connect"))
    )
    (net (code "103") (name "unconnected-(U4-VDD_SDIO-Pad26)") (class "Default")
      (node (ref "U4") (pin "26") (pinfunction "VDD_SDIO_26") (pintype "passive+no_connect"))
    )
    (net (code "104") (name "unconnected-(U4-XTAL_N_NC-Pad44)") (class "Default")
      (node (ref "U4") (pin "44") (pinfunction "XTAL_N_NC_44") (pintype "passive+no_connect"))
    )
    (net (code "105") (name "unconnected-(U4-XTAL_P_NC-Pad45)") (class "Default")
      (node (ref "U4") (pin "45") (pinfunction "XTAL_P_NC_45") (pintype "passive+no_connect"))
    )
    (net (code "106") (name "unconnected-(U6-Pad5)") (class "Default")
      (node (ref "U6") (pin "5") (pinfunction "5_5") (pintype "passive+no_connect"))
    )
    (net (code "107") (name "unconnected-(U6-Pad6)") (class "Default")
      (node (ref "U6") (pin "6") (pinfunction "6_6") (pintype "passive+no_connect"))
    )
    (net (code "108") (name "unconnected-(USB2-SBU1-PadA8)") (class "Default")
      (node (ref "USB2") (pin "A8") (pinfunction "SBU1_A8") (pintype "passive+no_connect"))
    )
    (net (code "109") (name "unconnected-(USB2-SBU2-PadB8)") (class "Default")
      (node (ref "USB2") (pin "B8") (pinfunction "SBU2_B8") (pintype "passive+no_connect"))
    )
  )
)
